# ESPSwitchBoard.net
KiCad netlist of a schematic drawn in EAGLE
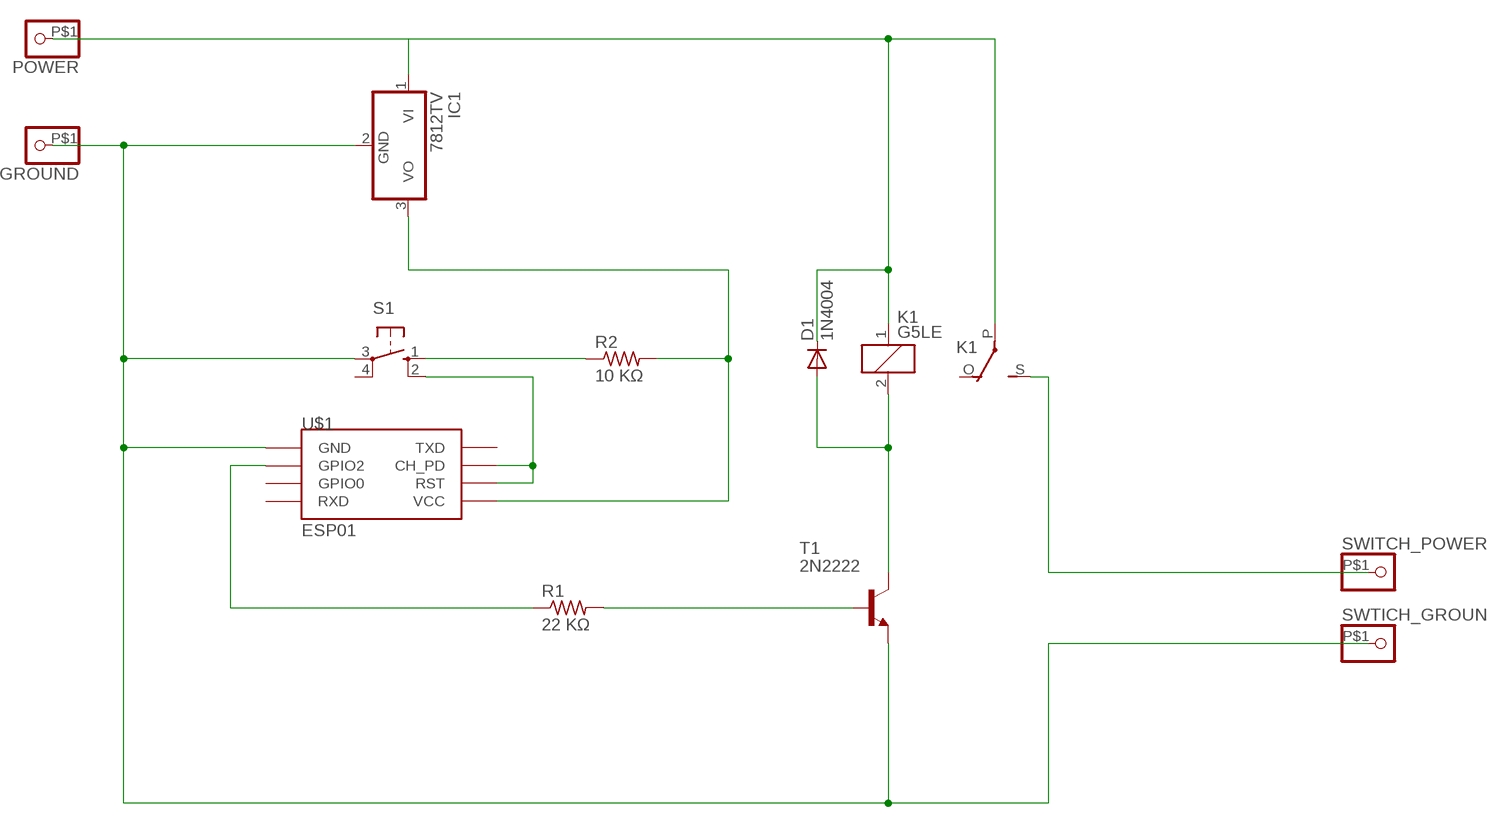
[diagram p0: schematic, sheet 1]

(export (version "E")
  (design (tool "Eeschema 10.0.6"))
  (components
    (comp (ref "D1")
      (value "1N4004")
      (footprint "eagle-import:DO41-10")
      (libsource (lib "eagle-import") (part "1N4004"))
    )
    (comp (ref "GROUND")
      (value "PINHD-1X1-BIGPOGO")
      (footprint "eagle-import:1X1-BIGPOGO")
      (libsource (lib "eagle-import") (part "PINHD-1X1-BIGPOGO"))
    )
    (comp (ref "IC1")
      (value "7812TV")
      (footprint "eagle-import:TO220V")
      (libsource (lib "eagle-import") (part "78TV12"))
    )
    (comp (ref "K1")
      (value "G5LE")
      (footprint "eagle-import:G5LE")
      (libsource (lib "eagle-import") (part "G5LE"))
    )
    (comp (ref "POWER")
      (value "PINHD-1X1-BIGPOGO")
      (footprint "eagle-import:1X1-BIGPOGO")
      (libsource (lib "eagle-import") (part "PINHD-1X1-BIGPOGO"))
    )
    (comp (ref "R1")
      (value "22 KΩ")
      (footprint "eagle-import:0207_10")
      (libsource (lib "eagle-import") (part "R-US_0207/10"))
    )
    (comp (ref "R2")
      (value "10 KΩ")
      (footprint "eagle-import:0207_10")
      (libsource (lib "eagle-import") (part "R-US_0207/10"))
    )
    (comp (ref "S1")
      (value "10-XX")
      (footprint "eagle-import:B3F-10XX")
      (fields (field (name "MPN") "B3F-1000"))
      (libsource (lib "eagle-import") (part "10-XX"))
    )
    (comp (ref "SWITCH_POWER")
      (value "PINHD-1X1-BIGPOGO")
      (footprint "eagle-import:1X1-BIGPOGO")
      (libsource (lib "eagle-import") (part "PINHD-1X1-BIGPOGO"))
    )
    (comp (ref "SWTICH_GROUND")
      (value "PINHD-1X1-BIGPOGO")
      (footprint "eagle-import:1X1-BIGPOGO")
      (libsource (lib "eagle-import") (part "PINHD-1X1-BIGPOGO"))
    )
    (comp (ref "T1")
      (value "2N2222")
      (footprint "eagle-import:TO92-EBC-OVAL")
      (libsource (lib "eagle-import") (part "2N2222"))
    )
    (comp (ref "U$1")
      (value "ESP01")
      (footprint "eagle-import:ESP01")
      (libsource (lib "eagle-import") (part "ESP01"))
    )
  )
  (nets
    (net (code "1") (name "Net-(D1-PadA)") (class "Default")
      (node (ref "D1") (pin "A") (pinfunction "A_A") (pintype "passive"))
      (node (ref "K1") (pin "2") (pinfunction "2_2") (pintype "passive"))
      (node (ref "T1") (pin "C") (pinfunction "C_C") (pintype "passive"))
    )
    (net (code "2") (name "Net-(GROUND-1)") (class "Default")
      (node (ref "GROUND") (pin "P$1") (pinfunction "1_P$1") (pintype "passive"))
      (node (ref "IC1") (pin "2") (pinfunction "GND_2") (pintype "passive"))
      (node (ref "S1") (pin "3") (pinfunction "P_3") (pintype "passive"))
      (node (ref "SWTICH_GROUND") (pin "P$1") (pinfunction "1_P$1") (pintype "passive"))
      (node (ref "T1") (pin "E") (pinfunction "E_E") (pintype "passive"))
      (node (ref "U$1") (pin "GND") (pinfunction "GND_GND") (pintype "bidirectional"))
    )
    (net (code "3") (name "Net-(IC1-VI)") (class "Default")
      (node (ref "D1") (pin "C") (pinfunction "C_C") (pintype "passive"))
      (node (ref "IC1") (pin "1") (pinfunction "VI_1") (pintype "input"))
      (node (ref "K1") (pin "1") (pinfunction "1_1") (pintype "passive"))
      (node (ref "K1") (pin "P") (pinfunction "P_P") (pintype "passive"))
      (node (ref "POWER") (pin "P$1") (pinfunction "1_P$1") (pintype "passive"))
    )
    (net (code "4") (name "Net-(IC1-VO)") (class "Default")
      (node (ref "IC1") (pin "3") (pinfunction "VO_3") (pintype "passive"))
      (node (ref "R2") (pin "2") (pinfunction "2_2") (pintype "passive"))
      (node (ref "U$1") (pin "VCC") (pinfunction "VCC_VCC") (pintype "bidirectional"))
    )
    (net (code "5") (name "Net-(R1-Pad1)") (class "Default")
      (node (ref "R1") (pin "1") (pinfunction "1_1") (pintype "passive"))
      (node (ref "U$1") (pin "GPIO2") (pinfunction "GPIO2_GPIO2") (pintype "bidirectional"))
    )
    (net (code "6") (name "Net-(R1-Pad2)") (class "Default")
      (node (ref "R1") (pin "2") (pinfunction "2_2") (pintype "passive"))
      (node (ref "T1") (pin "B") (pinfunction "B_B") (pintype "passive"))
    )
    (net (code "7") (name "Net-(S1-S)") (class "Default")
      (node (ref "R2") (pin "1") (pinfunction "1_1") (pintype "passive"))
      (node (ref "S1") (pin "1") (pinfunction "S_1") (pintype "passive"))
    )
    (net (code "8") (name "Net-(S1-S1)") (class "Default")
      (node (ref "S1") (pin "2") (pinfunction "S1_2") (pintype "passive"))
      (node (ref "U$1") (pin "CH_PD") (pinfunction "CH_PD_CH_PD") (pintype "bidirectional"))
      (node (ref "U$1") (pin "RST") (pinfunction "RST_RST") (pintype "bidirectional"))
    )
    (net (code "9") (name "Net-(SWITCH_POWER-1)") (class "Default")
      (node (ref "K1") (pin "S") (pinfunction "S_S") (pintype "passive"))
      (node (ref "SWITCH_POWER") (pin "P$1") (pinfunction "1_P$1") (pintype "passive"))
    )
    (net (code "10") (name "unconnected-(K1-PadO)") (class "Default")
      (node (ref "K1") (pin "O") (pinfunction "O_O") (pintype "passive"))
    )
    (net (code "11") (name "unconnected-(S1-P1-Pad4)") (class "Default")
      (node (ref "S1") (pin "4") (pinfunction "P1_4") (pintype "passive"))
    )
    (net (code "12") (name "unconnected-(U$1-PadGPIO0)") (class "Default")
      (node (ref "U$1") (pin "GPIO0") (pinfunction "GPIO0_GPIO0") (pintype "bidirectional"))
    )
    (net (code "13") (name "unconnected-(U$1-RXD-PadRX)") (class "Default")
      (node (ref "U$1") (pin "RX") (pinfunction "RXD_RX") (pintype "bidirectional"))
    )
    (net (code "14") (name "unconnected-(U$1-TXD-PadTX)") (class "Default")
      (node (ref "U$1") (pin "TX") (pinfunction "TXD_TX") (pintype "bidirectional"))
    )
  )
)
